# Power_circuit.net
KiCad netlist of a schematic drawn in Altium Designer
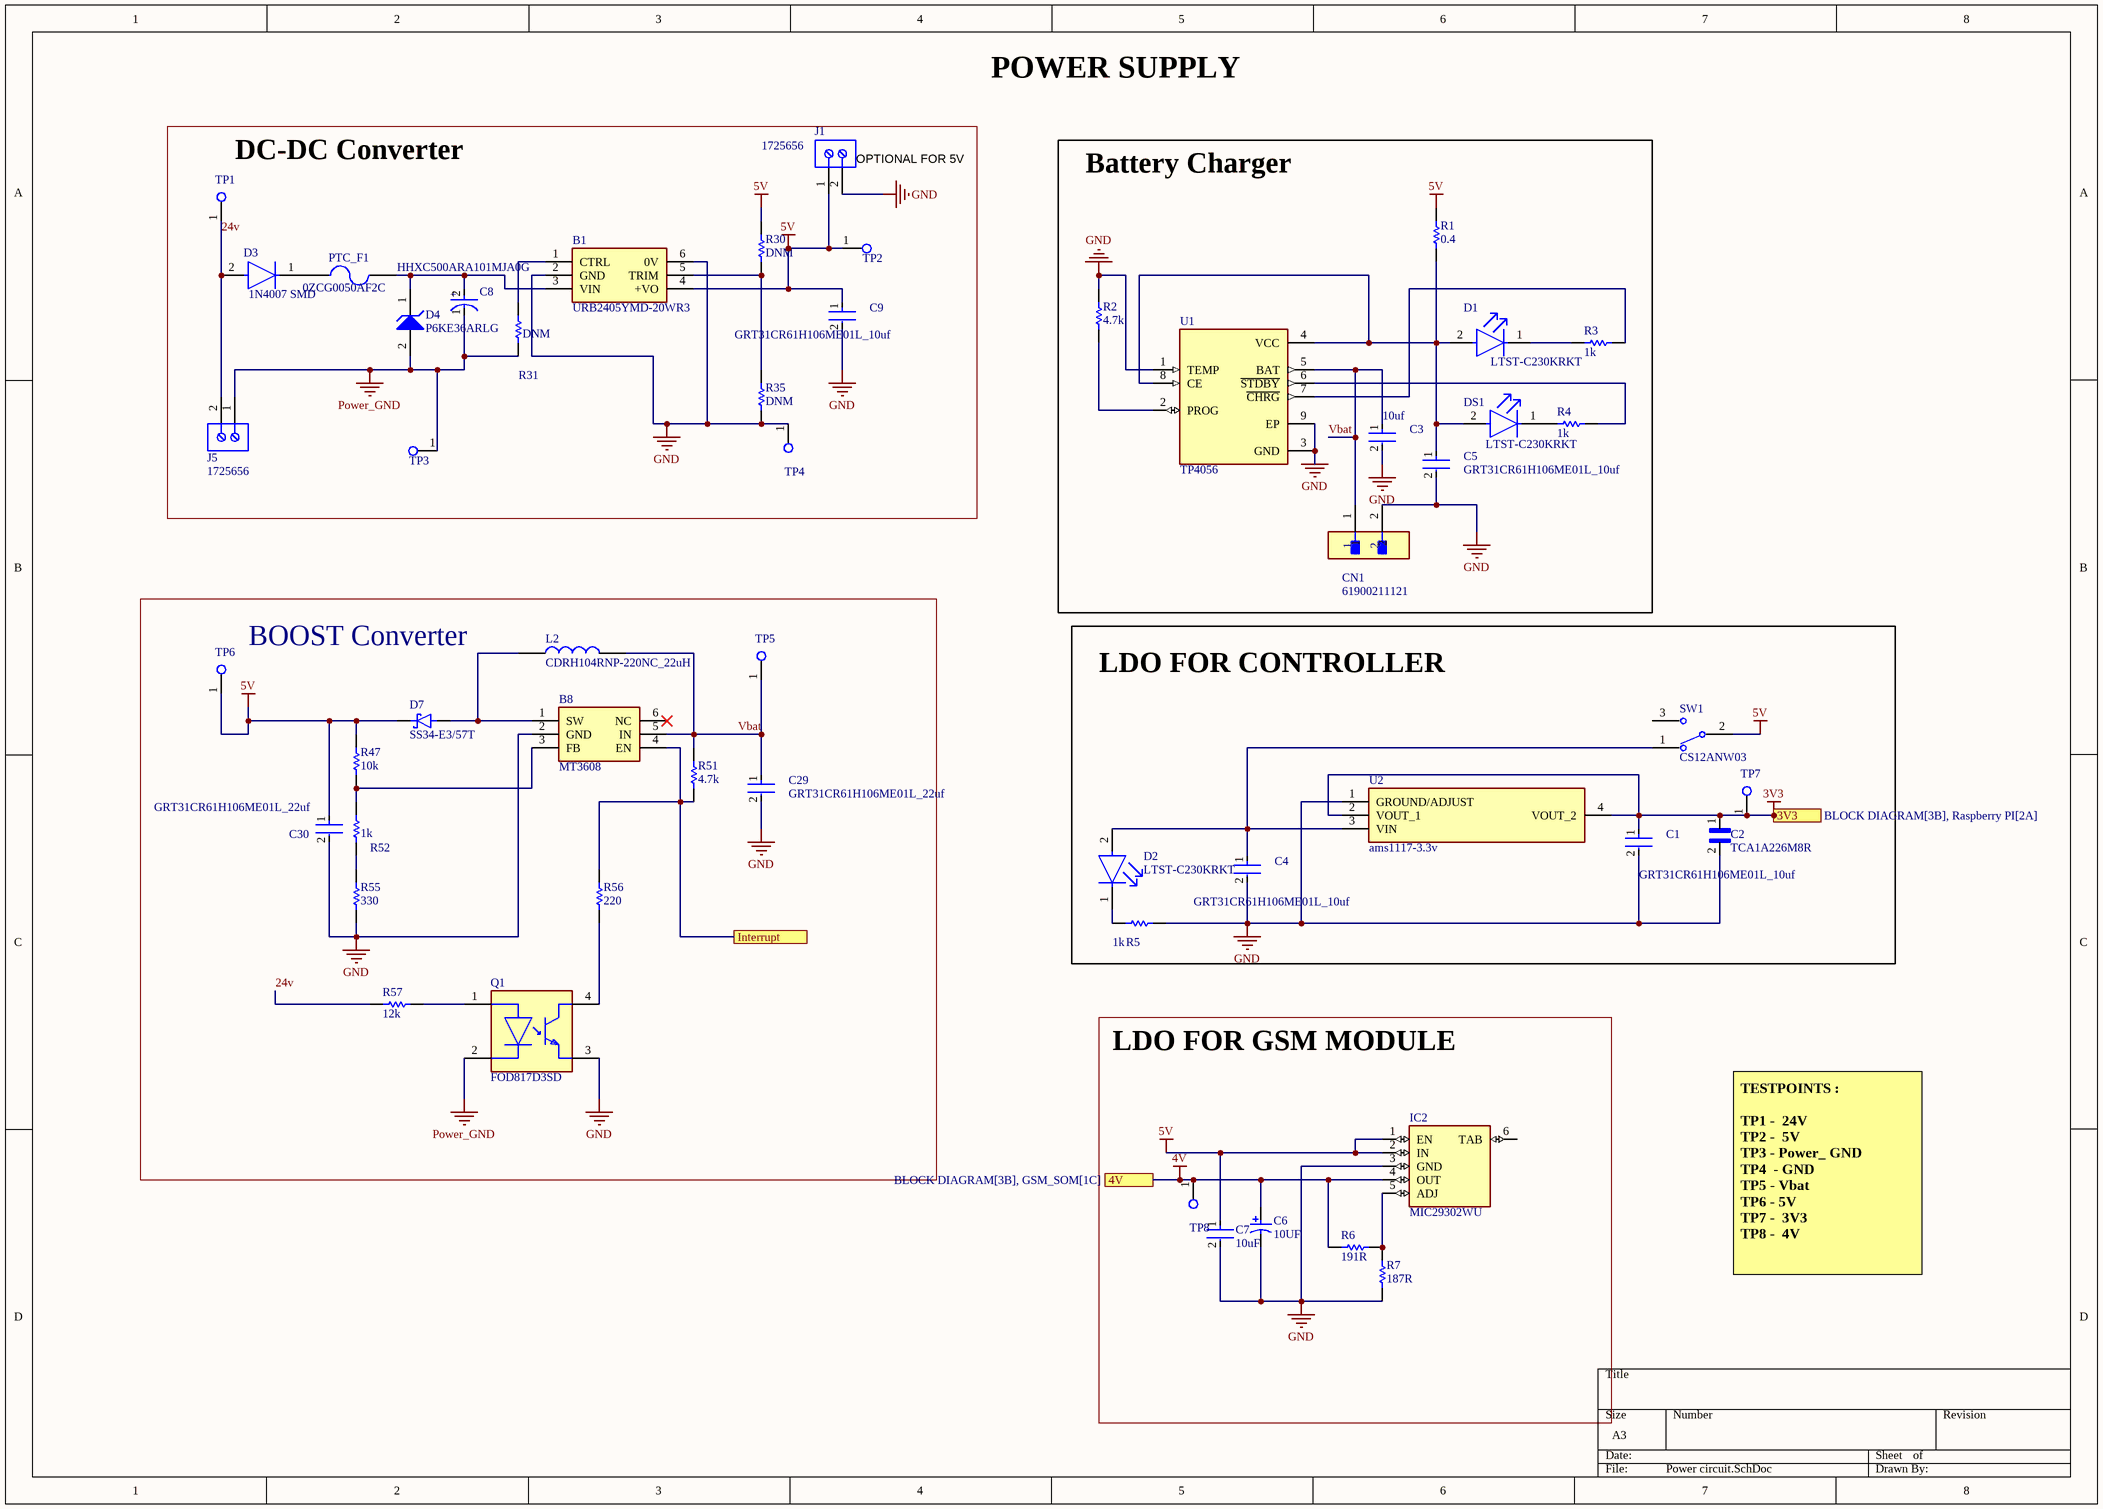
[diagram p0: Power circuit.SchDoc]

(export (version "E")
  (design (tool "Eeschema 10.0.6"))
  (components
    (comp (ref "B1")
      (value "URB2405YMD-20WR3")
      (footprint "URB2405YMD20WR3")
      (description "20W isolated DC-DC converter DIP package, Ultra-wide input and regulated single output")
      (libsource (lib "URB2405YMD-20WR3") (part "URB2405YMD-20WR3"))
    )
    (comp (ref "B8")
      (value "MT3608")
      (footprint "SOT95P280X145-6N")
      (description "High Efficiency 1.2MHz 2A Step Up Converter")
      (libsource (lib "MT3608") (part "MT3608"))
    )
    (comp (ref "C1")
      (value "GRT31CR61H106ME01L_10uf")
      (footprint "FP-GRT31C-0_2-MFG")
      (description "CAP CER 10UF 50V X5R 1206")
      (fields (field (name "TOLERANCE") "20%"))
      (libsource (lib "Altium Content Vault") (part "11868f565c42a9108669ba33697ecf6"))
    )
    (comp (ref "C2")
      (value "TCA1A226M8R")
      (footprint "RESC3216X65N")
      (description "22ÂµF Molded Tantalum Capacitors 10V 1206 (3216 Metric)")
      (fields (field (name "MF") "Rohm"))
      (libsource (lib "TCA1A226M8R") (part "TCA1A226M8R"))
    )
    (comp (ref "C3")
      (value "10uf")
      (footprint "FP-GRT31C-0_2-MFG")
      (description "CAP CER 10UF 50V X5R 1206")
      (fields (field (name "TOLERANCE") "20%"))
      (libsource (lib "Altium Content Vault") (part "11868f565c42a9108669ba33697ecf6"))
    )
    (comp (ref "C4")
      (value "GRT31CR61H106ME01L_10uf")
      (footprint "FP-GRT31C-0_2-MFG")
      (description "CAP CER 10UF 50V X5R 1206")
      (fields (field (name "TOLERANCE") "20%"))
      (libsource (lib "Altium Content Vault") (part "11868f565c42a9108669ba33697ecf6"))
    )
    (comp (ref "C5")
      (value "GRT31CR61H106ME01L_10uf")
      (footprint "FP-GRT31C-0_2-MFG")
      (description "CAP CER 10UF 50V X5R 1206")
      (fields (field (name "TOLERANCE") "20%"))
      (libsource (lib "Altium Content Vault") (part "11868f565c42a9108669ba33697ecf6"))
    )
    (comp (ref "C6")
      (value "10UF")
      (footprint "KEMT-A-3216-18-2_M")
      (description "Capacitor, Tantalum, 10 uF, +/- 10%, 10 V, -55 to 125 degC, 2-Pin SMD (1206), RoHS, Tape and Reel")
      (fields (field (name "TOLERANCE") "±10%") (field (name "MANUFACTURER") "Kemet"))
      (libsource (lib "Altium Content Vault") (part "CAP-P-2"))
    )
    (comp (ref "C7")
      (value "10uF")
      (footprint "FP-CL05A106MP5NUNC-MFG")
      (description "CAP CER 10UF 10V X5R 0402")
      (fields
        (field (name "OCTOPART") "https://octopart.com/cl05a106mp5nunc-samsung-22457395")
        (field (name "TOLERANCE") "20%")
      )
      (libsource (lib "Altium Content Vault") (part "b4654b650e69147ec39a6b967a45e02"))
    )
    (comp (ref "C8")
      (value "HHXC500ARA101MJA0G")
      (footprint "FP-HXC-ALA0-MFG")
      (description "CAP ALUM POLY 100UF 20% 50V SMD")
      (fields (field (name "TOLERANCE") "20%"))
      (libsource (lib "Altium Content Vault") (part "203bc49f2ac43e59fd269a8c329ed05"))
    )
    (comp (ref "C9")
      (value "GRT31CR61H106ME01L_10uf")
      (footprint "FP-GRT31C-0_2-MFG")
      (description "CAP CER 10UF 50V X5R 1206")
      (fields (field (name "TOLERANCE") "20%"))
      (libsource (lib "Altium Content Vault") (part "11868f565c42a9108669ba33697ecf6"))
    )
    (comp (ref "C29")
      (value "GRT31CR61H106ME01L_22uf")
      (footprint "FP-GRT31C-0_2-MFG")
      (description "CAP CER 10UF 50V X5R 1206")
      (fields (field (name "TOLERANCE") "20%"))
      (libsource (lib "Altium Content Vault") (part "11868f565c42a9108669ba33697ecf6"))
    )
    (comp (ref "C30")
      (value "GRT31CR61H106ME01L_22uf")
      (footprint "FP-GRT31C-0_2-MFG")
      (description "CAP CER 10UF 50V X5R 1206")
      (fields (field (name "TOLERANCE") "20%"))
      (libsource (lib "Altium Content Vault") (part "11868f565c42a9108669ba33697ecf6"))
    )
    (comp (ref "CN1")
      (value "61900211121")
      (footprint "FP-61900211121-MFG")
      (description "CONN HEADER VERT 2POS 2.54MM")
      (libsource (lib "Altium Content Vault") (part "3bc925449376181038e59eaffc5286c"))
    )
    (comp (ref "D1")
      (value "LTST-C230KRKT")
      (footprint "FP-LTST-C230KRKT-MFG")
      (description "LED RED CLEAR CHIP SMD")
      (libsource (lib "Altium Content Vault") (part "8706943c75ba83719d021d2fdc84c58"))
    )
    (comp (ref "D2")
      (value "LTST-C230KRKT")
      (footprint "FP-LTST-C230KRKT-MFG")
      (description "LED RED CLEAR CHIP SMD")
      (libsource (lib "Altium Content Vault") (part "8706943c75ba83719d021d2fdc84c58"))
    )
    (comp (ref "D3")
      (value "1N4007 SMD")
      (footprint "FP-1N4007_SMD-IPC_C")
      (description "Rectifier, 1Kv, 1A, Do-214Ac Rohs Compliant: Yes")
      (libsource (lib "Altium Content Vault") (part "d7152d700b627762746794eb795d46e"))
    )
    (comp (ref "D4")
      (value "P6KE36ARLG")
      (footprint "ONSC-SURMETIC40-2-017AA-01")
      (description "600 W Peak Power Transient Voltage Suppressor, 2-Pin Surmetic(TM) 40, Pb-Free, Tape and Reel")
      (fields (field (name "MANUFACTURER") "On Semiconductor"))
      (libsource (lib "Altium Content Vault") (part "ONSC-K1A2-2"))
    )
    (comp (ref "D7")
      (value "SS34-E3/57T")
      (footprint "DIOM7959X262N")
      (description "Diode Schottky 40 V 3A Surface Mount DO-214AB (SMC)")
      (fields (field (name "MF") "Vishay General Semiconductor"))
      (libsource (lib "SS34-E3_57T") (part "SS34-E3/57T"))
    )
    (comp (ref "DS1")
      (value "LTST-C230KRKT")
      (footprint "FP-LTST-C230KRKT-MFG")
      (description "LED RED CLEAR CHIP SMD")
      (libsource (lib "Altium Content Vault") (part "8706943c75ba83719d021d2fdc84c58"))
    )
    (comp (ref "IC2")
      (value "MIC29302WU")
      (footprint "MIC29302WU")
      (description "Linear Voltage Regulator IC Positive Adjustable 1 Output 3A TO-263-5")
      (fields (field (name "MF") "Microchip Technology"))
      (libsource (lib "MIC29302WU") (part "MIC29302WU"))
    )
    (comp (ref "J1")
      (value "1725656")
      (footprint "PHOE-1725656-2")
      (description "Male Header, Pitch 2.54 mm, 1 x 2 Position, Height 9 mm, Tail Length 3.5 mm")
      (fields (field (name "MANUFACTURER") "Phoenix Contact"))
      (libsource (lib "Altium Content Vault") (part "CN-1P-F-TB2"))
    )
    (comp (ref "J5")
      (value "1725656")
      (footprint "PHOE-1725656-2")
      (description "Male Header, Pitch 2.54 mm, 1 x 2 Position, Height 9 mm, Tail Length 3.5 mm")
      (fields (field (name "MANUFACTURER") "Phoenix Contact"))
      (libsource (lib "Altium Content Vault") (part "CN-1P-F-TB2"))
    )
    (comp (ref "L2")
      (value "CDRH104RNP-220NC_22uH")
      (footprint "INDPM102100X400N")
      (description "Fixed Inductors 22uH 2.5A")
      (fields
        (field (name "MANUFACTURER_PART_NUMBER") "CDRH104RNP-220NC")
        (field (name "MOUSER PART NUMBER") "851-CDRH104RNP-220NC")
      )
      (libsource (lib "CDRH104RNP-220NC") (part "CDRH104RNP-220NC"))
    )
    (comp (ref "PTC_F1")
      (value "0ZCG0050AF2C")
      (footprint "F1812")
      (description "PTC RESET FUSE 30V 500MA 1812")
      (fields (field (name "MFG") "Bel Fuse Inc."))
      (libsource (lib "Miscellaneous Devices") (part "Fuse 2"))
    )
    (comp (ref "Q1")
      (value "FOD817D3SD")
      (footprint "FP-709AH-MFG")
      (description "OPTOISOLATOR 5KV TRANSISTOR 4SMD")
      (fields
        (field (name "OCTOPART") "https://octopart.com/fod817d3sd-on+semiconductor-84327552")
        (field (name "MANUFACTURER") "ON Semiconductor")
      )
      (libsource (lib "Altium Content Vault") (part "1f1c6a0316ad75fed912f18075bb69c"))
    )
    (comp (ref "R1")
      (value "0.4")
      (footprint "RESC3216X60X45ML15T20")
      (description "Chip Resistor, 0 Ohm, +/- 5%, 0.25 W, -55 to 155 degC, 1206 (3216 Metric)")
      (fields (field (name "TOLERANCE") "5%") (field (name "POWER") "250mW"))
      (libsource (lib "Bannari Amman Institute of Technology") (part "RES-2"))
    )
    (comp (ref "R2")
      (value "4.7k")
      (footprint "RESC3216X60X45ML15T20")
      (description "Chip Resistor, 0 Ohm, +/- 5%, 0.25 W, -55 to 155 degC, 1206 (3216 Metric)")
      (fields (field (name "TOLERANCE") "5%") (field (name "POWER") "250mW"))
      (libsource (lib "Bannari Amman Institute of Technology") (part "RES-2"))
    )
    (comp (ref "R3")
      (value "1k")
      (footprint "RESC3216X60X45ML15T20")
      (description "Chip Resistor, 0 Ohm, +/- 5%, 0.25 W, -55 to 155 degC, 1206 (3216 Metric)")
      (fields (field (name "TOLERANCE") "5%") (field (name "POWER") "250mW"))
      (libsource (lib "Bannari Amman Institute of Technology") (part "RES-2"))
    )
    (comp (ref "R4")
      (value "1k")
      (footprint "RESC3216X60X45ML15T20")
      (description "Chip Resistor, 0 Ohm, +/- 5%, 0.25 W, -55 to 155 degC, 1206 (3216 Metric)")
      (fields (field (name "TOLERANCE") "5%") (field (name "POWER") "250mW"))
      (libsource (lib "Bannari Amman Institute of Technology") (part "RES-2"))
    )
    (comp (ref "R5")
      (value "1k")
      (footprint "RESC3216X60X45ML15T20")
      (description "Chip Resistor, 0 Ohm, +/- 5%, 0.25 W, -55 to 155 degC, 1206 (3216 Metric)")
      (fields (field (name "TOLERANCE") "5%") (field (name "POWER") "250mW"))
      (libsource (lib "Bannari Amman Institute of Technology") (part "RES-2"))
    )
    (comp (ref "R6")
      (value "191R")
      (footprint "RESC1005X40X25ML05T05")
      (fields (field (name "MANUFACTURER") "Panasonic") (field (name "PART NUMBER") "ERJ-2RKF1910X"))
      (libsource (lib "Altium Content Vault") (part "RES"))
    )
    (comp (ref "R7")
      (value "187R")
      (footprint "RESC1005X35X20LL05T10")
      (fields
        (field (name "PART NUMBER") "CPF0402B187RE1")
        (field (name "MANUFACTURER") "TE Connectivity / AMP")
      )
      (libsource (lib "Altium Content Vault") (part "RES"))
    )
    (comp (ref "R30")
      (value "Resistor 0R +/- 5% 1206 250 mW")
      (footprint "RESC3216X60X45ML15T20")
      (description "Chip Resistor, 0 Ohm, +/- 5%, 0.25 W, -55 to 155 degC, 1206 (3216 Metric)")
      (fields (field (name "TOLERANCE") "5%") (field (name "0") "DNM") (field (name "POWER") "250mW"))
      (libsource (lib "Bannari Amman Institute of Technology") (part "RES-2"))
    )
    (comp (ref "R31")
      (value "Resistor 0R +/- 5% 1206 250 mW")
      (footprint "RESC3216X60X45ML15T20")
      (description "Chip Resistor, 0 Ohm, +/- 5%, 0.25 W, -55 to 155 degC, 1206 (3216 Metric)")
      (fields (field (name "TOLERANCE") "5%") (field (name "0") "DNM") (field (name "POWER") "250mW"))
      (libsource (lib "Bannari Amman Institute of Technology") (part "RES-2"))
    )
    (comp (ref "R35")
      (value "Resistor 0R +/- 5% 1206 250 mW")
      (footprint "RESC3216X60X45ML15T20")
      (description "Chip Resistor, 0 Ohm, +/- 5%, 0.25 W, -55 to 155 degC, 1206 (3216 Metric)")
      (fields (field (name "TOLERANCE") "5%") (field (name "0") "DNM") (field (name "POWER") "250mW"))
      (libsource (lib "Bannari Amman Institute of Technology") (part "RES-2"))
    )
    (comp (ref "R47")
      (value "10k")
      (footprint "RESC3216X60X45ML15T20")
      (description "Chip Resistor, 0 Ohm, +/- 5%, 0.25 W, -55 to 155 degC, 1206 (3216 Metric)")
      (fields (field (name "TOLERANCE") "5%") (field (name "POWER") "250mW"))
      (libsource (lib "Bannari Amman Institute of Technology") (part "RES-2"))
    )
    (comp (ref "R51")
      (value "4.7k")
      (footprint "RESC3216X60X45ML15T20")
      (description "Chip Resistor, 0 Ohm, +/- 5%, 0.25 W, -55 to 155 degC, 1206 (3216 Metric)")
      (fields (field (name "TOLERANCE") "5%") (field (name "POWER") "250mW"))
      (libsource (lib "Bannari Amman Institute of Technology") (part "RES-2"))
    )
    (comp (ref "R52")
      (value "1k")
      (footprint "RESC3216X60X45ML15T20")
      (description "Chip Resistor, 0 Ohm, +/- 5%, 0.25 W, -55 to 155 degC, 1206 (3216 Metric)")
      (fields (field (name "TOLERANCE") "5%") (field (name "POWER") "250mW"))
      (libsource (lib "Bannari Amman Institute of Technology") (part "RES-2"))
    )
    (comp (ref "R55")
      (value "330")
      (footprint "RESC3216X60X45ML15T20")
      (description "Chip Resistor, 0 Ohm, +/- 5%, 0.25 W, -55 to 155 degC, 1206 (3216 Metric)")
      (fields (field (name "TOLERANCE") "5%") (field (name "POWER") "250mW"))
      (libsource (lib "Bannari Amman Institute of Technology") (part "RES-2"))
    )
    (comp (ref "R56")
      (value "220")
      (footprint "RESC3216X60X45ML15T20")
      (description "Chip Resistor, 0 Ohm, +/- 5%, 0.25 W, -55 to 155 degC, 1206 (3216 Metric)")
      (fields (field (name "TOLERANCE") "5%") (field (name "POWER") "250mW"))
      (libsource (lib "Bannari Amman Institute of Technology") (part "RES-2"))
    )
    (comp (ref "R57")
      (value "12k")
      (footprint "RESC3216X60X45ML15T20")
      (description "Chip Resistor, 0 Ohm, +/- 5%, 0.25 W, -55 to 155 degC, 1206 (3216 Metric)")
      (fields (field (name "TOLERANCE") "5%") (field (name "POWER") "250mW"))
      (libsource (lib "Bannari Amman Institute of Technology") (part "RES-2"))
    )
    (comp (ref "SW1")
      (value "CS12ANW03")
      (footprint "FP-CS12ANW03-MFG")
      (description "SWITCH SLIDE SPDT 3A 125V")
      (libsource (lib "Altium Content Vault") (part "12161840acc88c497b895bf2e19a5b1"))
    )
    (comp (ref "TP1")
      (value "Test Point")
      (footprint "TEST_POINT_SMD_30D")
      (description "TEST POINT PC MINI .040\"D RED")
      (fields (field (name "MFG") "Keystone"))
      (libsource (lib "HTT SoM - Sept 7 2016 V1P2 ") (part "TP"))
    )
    (comp (ref "TP2")
      (value "Test Point")
      (footprint "TEST_POINT_SMD_30D")
      (description "TEST POINT PC MINI .040\"D RED")
      (fields (field (name "MFG") "Keystone"))
      (libsource (lib "HTT SoM - Sept 7 2016 V1P2 ") (part "TP"))
    )
    (comp (ref "TP3")
      (value "Test Point")
      (footprint "TEST_POINT_SMD_30D")
      (description "TEST POINT PC MINI .040\"D RED")
      (fields (field (name "MFG") "Keystone"))
      (libsource (lib "HTT SoM - Sept 7 2016 V1P2 ") (part "TP"))
    )
    (comp (ref "TP4")
      (value "Test Point")
      (footprint "TEST_POINT_SMD_30D")
      (description "TEST POINT PC MINI .040\"D RED")
      (fields (field (name "MFG") "Keystone"))
      (libsource (lib "HTT SoM - Sept 7 2016 V1P2 ") (part "TP"))
    )
    (comp (ref "TP5")
      (value "Test Point")
      (footprint "TEST_POINT_SMD_30D")
      (description "TEST POINT PC MINI .040\"D RED")
      (fields (field (name "MFG") "Keystone"))
      (libsource (lib "HTT SoM - Sept 7 2016 V1P2 ") (part "TP"))
    )
    (comp (ref "TP6")
      (value "Test Point")
      (footprint "TEST_POINT_SMD_30D")
      (description "TEST POINT PC MINI .040\"D RED")
      (fields (field (name "MFG") "Keystone"))
      (libsource (lib "HTT SoM - Sept 7 2016 V1P2 ") (part "TP"))
    )
    (comp (ref "TP7")
      (value "Test Point")
      (footprint "TEST_POINT_SMD_30D")
      (description "TEST POINT PC MINI .040\"D RED")
      (fields (field (name "MFG") "Keystone"))
      (libsource (lib "HTT SoM - Sept 7 2016 V1P2 ") (part "TP"))
    )
    (comp (ref "TP8")
      (value "Test Point")
      (footprint "TEST_POINT_SMD_30D")
      (description "TEST POINT PC MINI .040\"D RED")
      (fields (field (name "MFG") "Keystone"))
      (libsource (lib "HTT SoM - Sept 7 2016 V1P2 ") (part "TP"))
    )
    (comp (ref "U1")
      (value "TP4056")
      (footprint "SOP127P600X175-9N")
      (description "Complete single cell Li-Ion battery with a constant current / constant voltage linear charger")
      (fields (field (name "MF") "NanJing Top Power ASIC Corp."))
      (libsource (lib "TP4056") (part "TP4056"))
    )
    (comp (ref "U2")
      (value "ams1117-3.3v")
      (footprint "SOT229P700X180-4N")
      (description "1A LOW DROPOUT VOLTAGE REGULATOR, SOT-223")
      (libsource (lib "ams1117-3.3v") (part "ams1117-3.3v"))
    )
  )
  (nets
    (net (code "1") (name "/24v") (class "Default")
      (node (ref "D3") (pin "2") (pinfunction "A_2") (pintype "passive"))
      (node (ref "J5") (pin "2") (pinfunction "2_2") (pintype "passive"))
      (node (ref "R57") (pin "2") (pinfunction "2_2") (pintype "passive"))
      (node (ref "TP1") (pin "1") (pintype "passive"))
    )
    (net (code "2") (name "/Interrupt") (class "Default")
      (node (ref "B8") (pin "4") (pinfunction "EN_4") (pintype "passive"))
      (node (ref "R51") (pin "1") (pinfunction "1_1") (pintype "passive"))
      (node (ref "R56") (pin "2") (pinfunction "2_2") (pintype "passive"))
    )
    (net (code "3") (name "/Vbat") (class "Default")
      (node (ref "B8") (pin "5") (pinfunction "IN_5") (pintype "passive"))
      (node (ref "C29") (pin "1") (pinfunction "1_1") (pintype "passive"))
      (node (ref "C3") (pin "1") (pinfunction "1_1") (pintype "passive"))
      (node (ref "CN1") (pin "1") (pinfunction "1_1") (pintype "passive"))
      (node (ref "L2") (pin "2") (pinfunction "2_2") (pintype "passive"))
      (node (ref "R51") (pin "2") (pinfunction "2_2") (pintype "passive"))
      (node (ref "TP5") (pin "1") (pintype "passive"))
      (node (ref "U1") (pin "5") (pinfunction "BAT_5") (pintype "output"))
    )
    (net (code "4") (name "3V3") (class "Default")
      (node (ref "C1") (pin "1") (pinfunction "1_1") (pintype "passive"))
      (node (ref "C2") (pin "1") (pinfunction "1_1") (pintype "passive"))
      (node (ref "TP7") (pin "1") (pintype "passive"))
      (node (ref "U2") (pin "2") (pinfunction "VOUT_1_2") (pintype "passive"))
      (node (ref "U2") (pin "4") (pinfunction "VOUT_2_4") (pintype "passive"))
    )
    (net (code "5") (name "4V") (class "Default")
      (node (ref "C6") (pin "1") (pinfunction "1_1") (pintype "passive"))
      (node (ref "IC2") (pin "4") (pinfunction "OUT_4") (pintype "bidirectional"))
      (node (ref "R6") (pin "1") (pinfunction "1_1") (pintype "passive"))
      (node (ref "TP8") (pin "1") (pintype "passive"))
    )
    (net (code "6") (name "5V") (class "Default")
      (node (ref "B1") (pin "4") (pinfunction "+VO_4") (pintype "passive"))
      (node (ref "C30") (pin "1") (pinfunction "1_1") (pintype "passive"))
      (node (ref "C7") (pin "1") (pinfunction "1_1") (pintype "passive"))
      (node (ref "C9") (pin "1") (pinfunction "1_1") (pintype "passive"))
      (node (ref "D7") (pin "C") (pinfunction "C_C") (pintype "passive"))
      (node (ref "IC2") (pin "1") (pinfunction "EN_1") (pintype "bidirectional"))
      (node (ref "IC2") (pin "2") (pinfunction "IN_2") (pintype "bidirectional"))
      (node (ref "J1") (pin "1") (pinfunction "1_1") (pintype "passive"))
      (node (ref "R1") (pin "2") (pinfunction "2_2") (pintype "passive"))
      (node (ref "R30") (pin "2") (pinfunction "2_2") (pintype "passive"))
      (node (ref "R47") (pin "2") (pinfunction "2_2") (pintype "passive"))
      (node (ref "SW1") (pin "2") (pinfunction "2(COM)_2") (pintype "passive"))
      (node (ref "TP2") (pin "1") (pintype "passive"))
      (node (ref "TP6") (pin "1") (pintype "passive"))
    )
    (net (code "7") (name "GND") (class "Default")
      (node (ref "B1") (pin "2") (pinfunction "GND_2") (pintype "passive"))
      (node (ref "B1") (pin "6") (pinfunction "0V_6") (pintype "passive"))
      (node (ref "B8") (pin "2") (pinfunction "GND_2") (pintype "passive"))
      (node (ref "C1") (pin "2") (pinfunction "2_2") (pintype "passive"))
      (node (ref "C2") (pin "2") (pinfunction "2_2") (pintype "passive"))
      (node (ref "C29") (pin "2") (pinfunction "2_2") (pintype "passive"))
      (node (ref "C3") (pin "2") (pinfunction "2_2") (pintype "passive"))
      (node (ref "C30") (pin "2") (pinfunction "2_2") (pintype "passive"))
      (node (ref "C4") (pin "2") (pinfunction "2_2") (pintype "passive"))
      (node (ref "C5") (pin "2") (pinfunction "2_2") (pintype "passive"))
      (node (ref "C6") (pin "2") (pinfunction "2_2") (pintype "passive"))
      (node (ref "C7") (pin "2") (pinfunction "2_2") (pintype "passive"))
      (node (ref "C9") (pin "2") (pinfunction "2_2") (pintype "passive"))
      (node (ref "CN1") (pin "2") (pinfunction "2_2") (pintype "passive"))
      (node (ref "IC2") (pin "3") (pinfunction "GND_3") (pintype "bidirectional"))
      (node (ref "J1") (pin "2") (pinfunction "2_2") (pintype "passive"))
      (node (ref "Q1") (pin "3") (pinfunction "E_3") (pintype "passive"))
      (node (ref "R2") (pin "2") (pinfunction "2_2") (pintype "passive"))
      (node (ref "R35") (pin "1") (pinfunction "1_1") (pintype "passive"))
      (node (ref "R5") (pin "1") (pinfunction "1_1") (pintype "passive"))
      (node (ref "R55") (pin "1") (pinfunction "1_1") (pintype "passive"))
      (node (ref "R7") (pin "1") (pinfunction "1_1") (pintype "passive"))
      (node (ref "TP4") (pin "1") (pintype "passive"))
      (node (ref "U1") (pin "1") (pinfunction "TEMP_1") (pintype "input"))
      (node (ref "U1") (pin "3") (pinfunction "GND_3") (pintype "power_in"))
      (node (ref "U1") (pin "9") (pinfunction "EP_9") (pintype "passive"))
      (node (ref "U2") (pin "1") (pinfunction "GROUND/ADJUST_1") (pintype "passive"))
    )
    (net (code "8") (name "Net-(B1-CTRL)") (class "Default")
      (node (ref "B1") (pin "1") (pinfunction "CTRL_1") (pintype "passive"))
      (node (ref "R31") (pin "2") (pinfunction "2_2") (pintype "passive"))
    )
    (net (code "9") (name "Net-(B1-TRIM)") (class "Default")
      (node (ref "B1") (pin "5") (pinfunction "TRIM_5") (pintype "passive"))
      (node (ref "R30") (pin "1") (pinfunction "1_1") (pintype "passive"))
      (node (ref "R35") (pin "2") (pinfunction "2_2") (pintype "passive"))
    )
    (net (code "10") (name "Net-(B1-VIN)") (class "Default")
      (node (ref "B1") (pin "3") (pinfunction "VIN_3") (pintype "passive"))
      (node (ref "C8") (pin "2") (pinfunction "A_2") (pintype "passive"))
      (node (ref "D4") (pin "1") (pinfunction "K_1") (pintype "passive"))
      (node (ref "PTC_F1") (pin "2") (pinfunction "2_2") (pintype "passive"))
    )
    (net (code "11") (name "Net-(B8-FB)") (class "Default")
      (node (ref "B8") (pin "3") (pinfunction "FB_3") (pintype "passive"))
      (node (ref "R47") (pin "1") (pinfunction "1_1") (pintype "passive"))
      (node (ref "R52") (pin "2") (pinfunction "2_2") (pintype "passive"))
    )
    (net (code "12") (name "Net-(B8-SW)") (class "Default")
      (node (ref "B8") (pin "1") (pinfunction "SW_1") (pintype "passive"))
      (node (ref "D7") (pin "A") (pinfunction "A_A") (pintype "passive"))
      (node (ref "L2") (pin "1") (pinfunction "1_1") (pintype "passive"))
    )
    (net (code "13") (name "Net-(D1-A)") (class "Default")
      (node (ref "C5") (pin "1") (pinfunction "1_1") (pintype "passive"))
      (node (ref "D1") (pin "2") (pinfunction "A_2") (pintype "passive"))
      (node (ref "DS1") (pin "2") (pinfunction "A_2") (pintype "passive"))
      (node (ref "R1") (pin "1") (pinfunction "1_1") (pintype "passive"))
      (node (ref "U1") (pin "4") (pinfunction "VCC_4") (pintype "power_in"))
      (node (ref "U1") (pin "8") (pinfunction "CE_8") (pintype "input"))
    )
    (net (code "14") (name "Net-(D1-C)") (class "Default")
      (node (ref "D1") (pin "1") (pinfunction "C_1") (pintype "passive"))
      (node (ref "R3") (pin "2") (pinfunction "2_2") (pintype "passive"))
    )
    (net (code "15") (name "Net-(D2-A)") (class "Default")
      (node (ref "C4") (pin "1") (pinfunction "1_1") (pintype "passive"))
      (node (ref "D2") (pin "2") (pinfunction "A_2") (pintype "passive"))
      (node (ref "SW1") (pin "1") (pinfunction "1_1") (pintype "passive"))
      (node (ref "U2") (pin "3") (pinfunction "VIN_3") (pintype "passive"))
    )
    (net (code "16") (name "Net-(D2-C)") (class "Default")
      (node (ref "D2") (pin "1") (pinfunction "C_1") (pintype "passive"))
      (node (ref "R5") (pin "2") (pinfunction "2_2") (pintype "passive"))
    )
    (net (code "17") (name "Net-(D3-C)") (class "Default")
      (node (ref "D3") (pin "1") (pinfunction "C_1") (pintype "passive"))
      (node (ref "PTC_F1") (pin "1") (pinfunction "1_1") (pintype "passive"))
    )
    (net (code "18") (name "Net-(DS1-C)") (class "Default")
      (node (ref "DS1") (pin "1") (pinfunction "C_1") (pintype "passive"))
      (node (ref "R4") (pin "2") (pinfunction "2_2") (pintype "passive"))
    )
    (net (code "19") (name "Net-(IC2-ADJ)") (class "Default")
      (node (ref "IC2") (pin "5") (pinfunction "ADJ_5") (pintype "bidirectional"))
      (node (ref "R6") (pin "2") (pinfunction "2_2") (pintype "passive"))
      (node (ref "R7") (pin "2") (pinfunction "2_2") (pintype "passive"))
    )
    (net (code "20") (name "Net-(Q1-A)") (class "Default")
      (node (ref "Q1") (pin "1") (pinfunction "A_1") (pintype "passive"))
      (node (ref "R57") (pin "1") (pinfunction "1_1") (pintype "passive"))
    )
    (net (code "21") (name "Net-(Q1-C-Pad4)") (class "Default")
      (node (ref "Q1") (pin "4") (pinfunction "C_4") (pintype "passive"))
      (node (ref "R56") (pin "1") (pinfunction "1_1") (pintype "passive"))
    )
    (net (code "22") (name "Net-(R52-Pad1)") (class "Default")
      (node (ref "R52") (pin "1") (pinfunction "1_1") (pintype "passive"))
      (node (ref "R55") (pin "2") (pinfunction "2_2") (pintype "passive"))
    )
    (net (code "23") (name "Net-(U1-PROG)") (class "Default")
      (node (ref "R2") (pin "1") (pinfunction "1_1") (pintype "passive"))
      (node (ref "U1") (pin "2") (pinfunction "PROG_2") (pintype "bidirectional"))
    )
    (net (code "24") (name "Net-(U1-~{CHRG})") (class "Default")
      (node (ref "R3") (pin "1") (pinfunction "1_1") (pintype "passive"))
      (node (ref "U1") (pin "7") (pinfunction "~{CHRG}_7") (pintype "output"))
    )
    (net (code "25") (name "Net-(U1-~{STDBY})") (class "Default")
      (node (ref "R4") (pin "1") (pinfunction "1_1") (pintype "passive"))
      (node (ref "U1") (pin "6") (pinfunction "~{STDBY}_6") (pintype "output"))
    )
    (net (code "26") (name "Power_GND") (class "Default")
      (node (ref "C8") (pin "1") (pinfunction "C_1") (pintype "passive"))
      (node (ref "D4") (pin "2") (pinfunction "A_2") (pintype "passive"))
      (node (ref "J5") (pin "1") (pinfunction "1_1") (pintype "passive"))
      (node (ref "Q1") (pin "2") (pinfunction "C_2") (pintype "passive"))
      (node (ref "R31") (pin "1") (pinfunction "1_1") (pintype "passive"))
      (node (ref "TP3") (pin "1") (pintype "passive"))
    )
    (net (code "27") (name "unconnected-(B8-NC-Pad6)") (class "Default")
      (node (ref "B8") (pin "6") (pinfunction "NC_6") (pintype "passive+no_connect"))
    )
    (net (code "28") (name "unconnected-(IC2-TAB-Pad6)") (class "Default")
      (node (ref "IC2") (pin "6") (pinfunction "TAB_6") (pintype "bidirectional"))
    )
    (net (code "29") (name "unconnected-(SW1-Pad3)") (class "Default")
      (node (ref "SW1") (pin "3") (pinfunction "3_3") (pintype "passive"))
    )
  )
)
